# ProPrj_esp32_pressure_sensor_2026-01-26.net
KiCad netlist of a schematic drawn in EasyEDA Pro
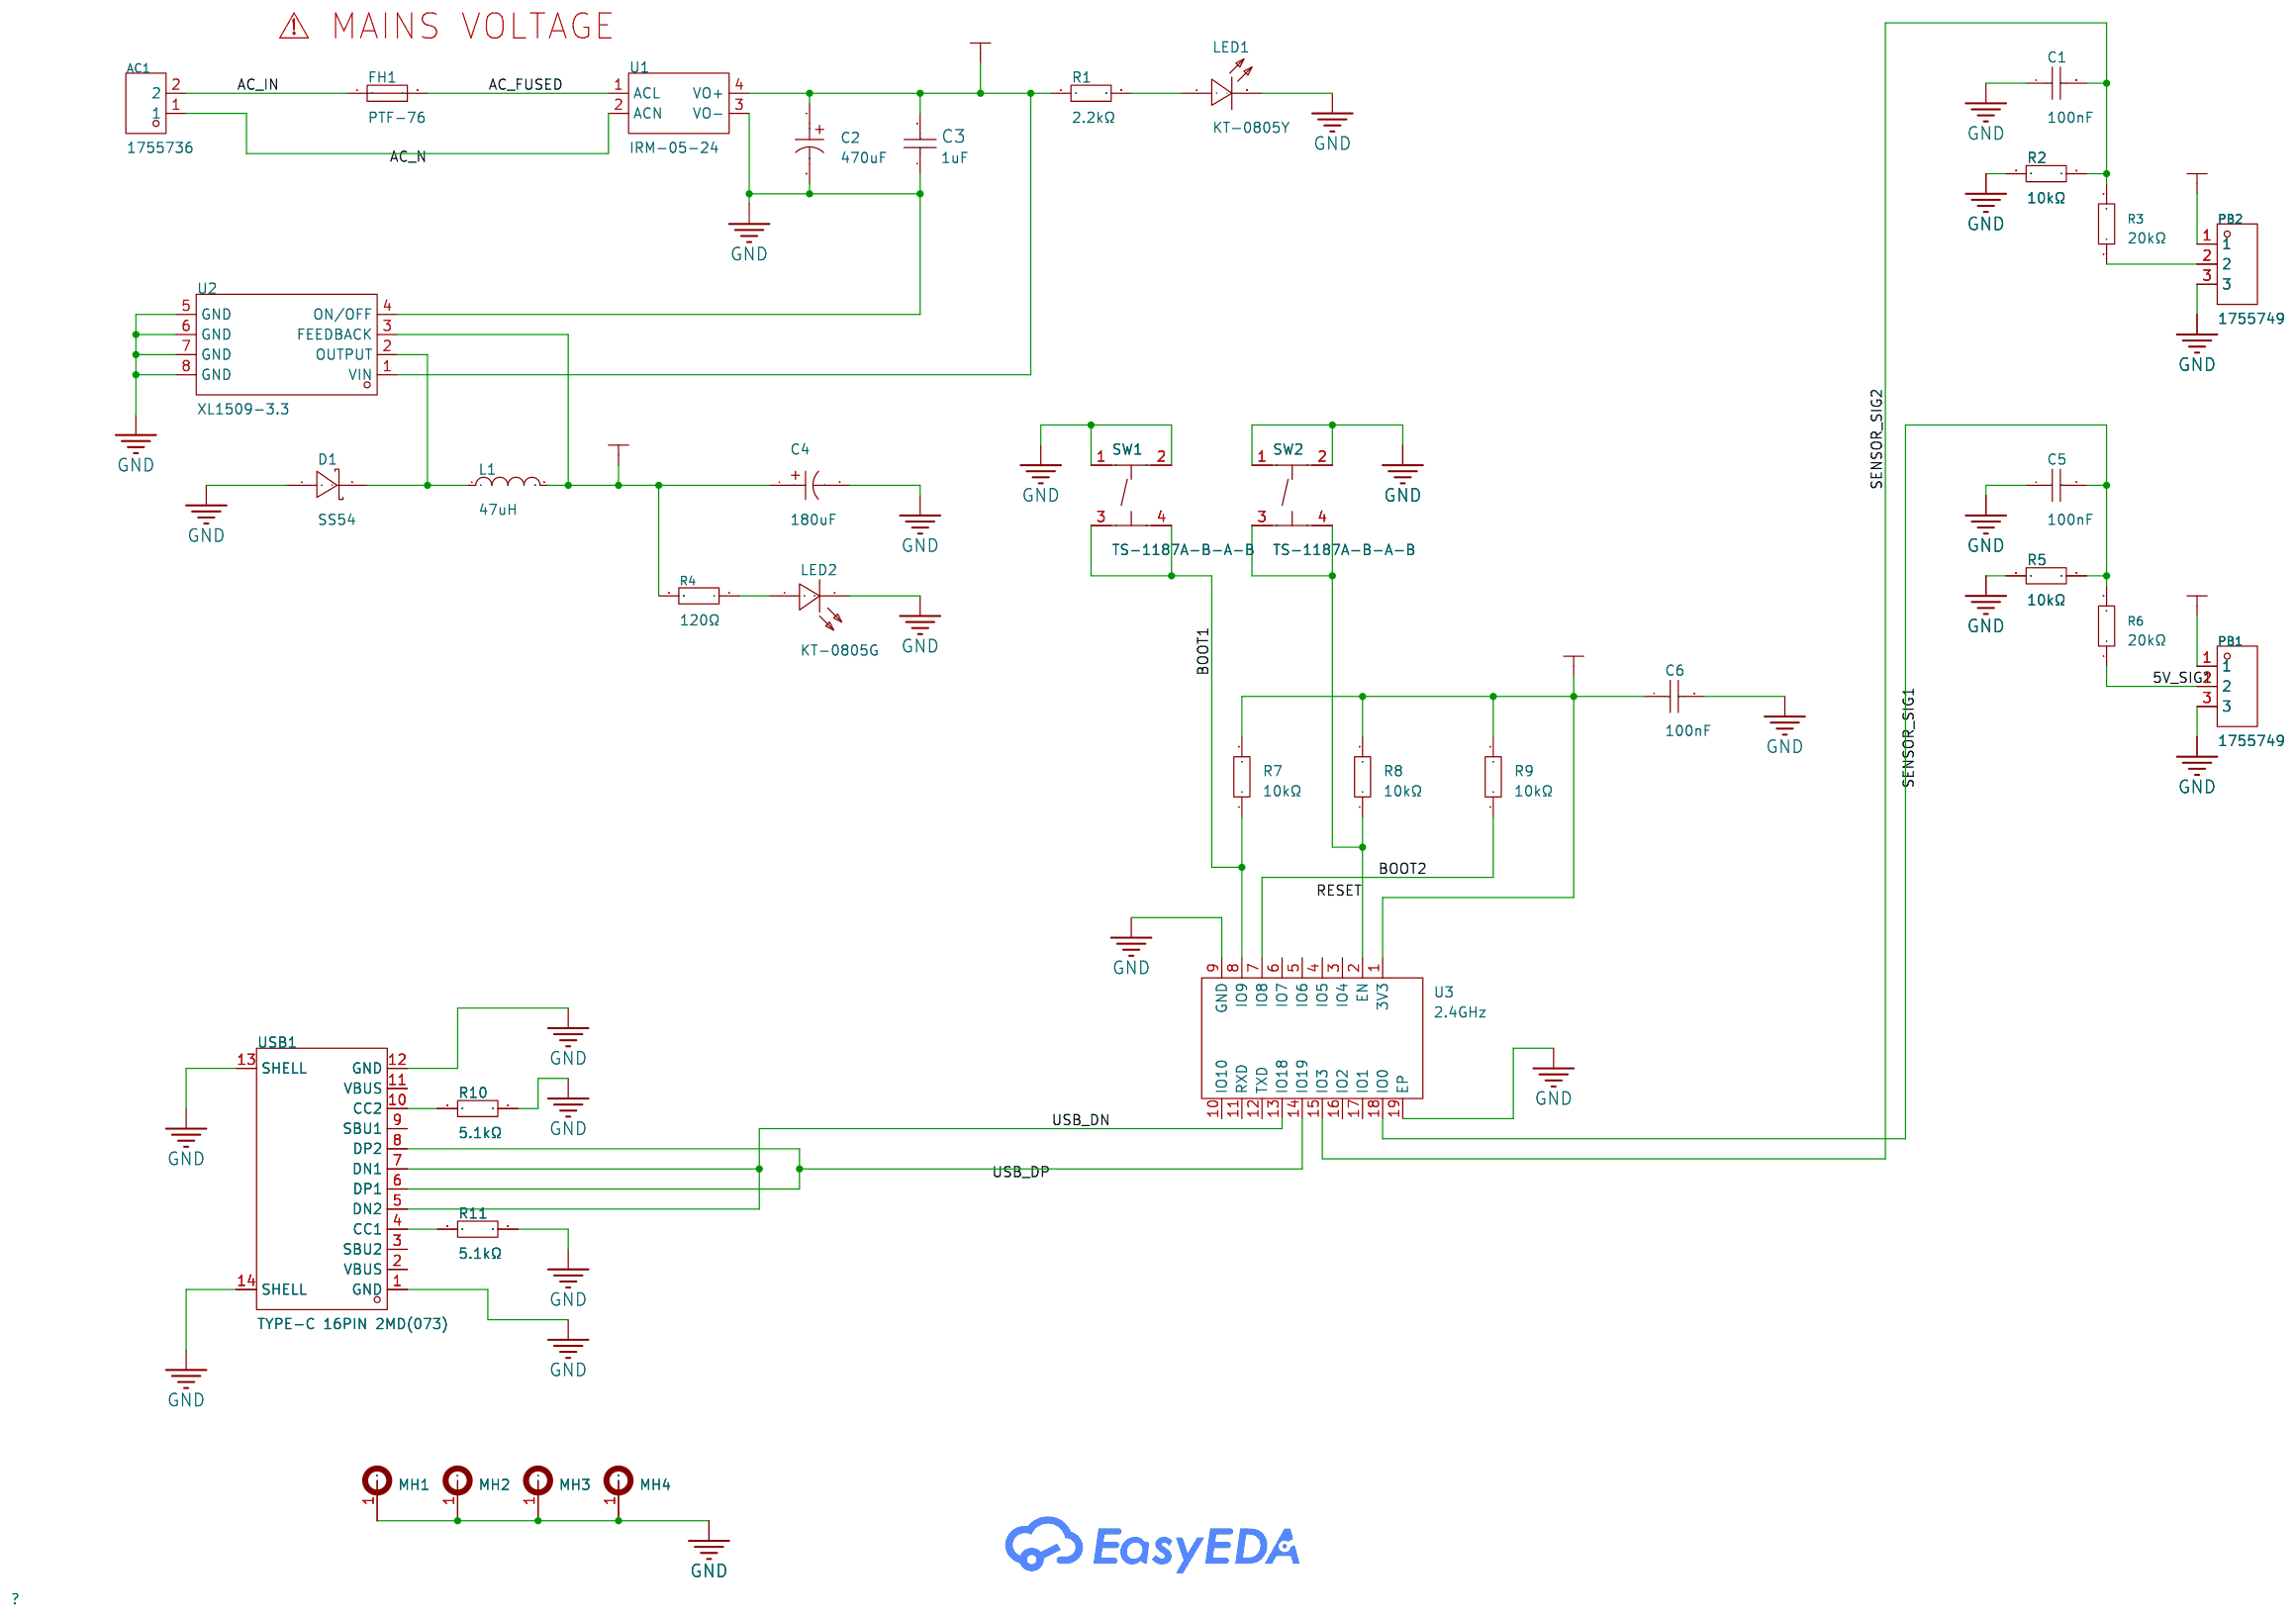
[diagram p0: schematic sheet]

(export (version "E")
  (design (tool "Eeschema 10.0.6"))
  (components
    (comp (ref "AC1")
      (value "1755736")
      (footprint "easyedapro:CONN-TH_1755736")
      (fields (field (name "Manufacturer") "Phoenix Contact(菲尼克斯)"))
      (libsource (lib "easyedapro") (part "1755736"))
    )
    (comp (ref "C1")
      (value "100nF")
      (footprint "easyedapro:C0805")
      (description "Capacitance:100nF Tolerance:±10% Tolerance:±10% Voltage Rating:100V Temperature Coefficient:X7R")
      (fields
        (field (name "Manufacturer Part") "CL21B104KCFNNNE")
        (field (name "Manufacturer") "SAMSUNG(三星)")
      )
      (libsource (lib "easyedapro") (part "CL21B104KCFNNNE"))
    )
    (comp (ref "C2")
      (value "470uF")
      (footprint "easyedapro:CAP-SMD_BD10.0-L10.3-W10.3-LS11.0-FD")
      (fields (field (name "Manufacturer Part") "JVE25V470M10X10") (field (name "Manufacturer") "JIERR(捷而瑞)"))
      (libsource (lib "easyedapro") (part "JVE25V470M10X10"))
    )
    (comp (ref "C3")
      (value "1uF")
      (footprint "easyedapro:C0805")
      (description "Capacitance:1uF Tolerance:±10% Tolerance:±10% Voltage Rating:50V Temperature Coefficient:X7R")
      (fields
        (field (name "Manufacturer Part") "CL21B105KBFNNNE")
        (field (name "Manufacturer") "SAMSUNG(三星)")
      )
      (libsource (lib "easyedapro") (part "CL21B105KBFNNNE"))
    )
    (comp (ref "C4")
      (value "180uF")
      (footprint "easyedapro:CAP-SMD_BD6.3-L6.6-W6.6-LS7.4-FD")
      (fields (field (name "Manufacturer Part") "RVT25V180M6X8") (field (name "Manufacturer") "JIERR(捷而瑞)"))
      (libsource (lib "easyedapro") (part "RVT25V180M6X8"))
    )
    (comp (ref "C5")
      (value "100nF")
      (footprint "easyedapro:C0805")
      (description "Capacitance:100nF Tolerance:±10% Tolerance:±10% Voltage Rating:100V Temperature Coefficient:X7R")
      (fields
        (field (name "Manufacturer Part") "CL21B104KCFNNNE")
        (field (name "Manufacturer") "SAMSUNG(三星)")
      )
      (libsource (lib "easyedapro") (part "CL21B104KCFNNNE"))
    )
    (comp (ref "C6")
      (value "100nF")
      (footprint "easyedapro:C0805")
      (description "Capacitance:100nF Tolerance:±10% Tolerance:±10% Voltage Rating:100V Temperature Coefficient:X7R")
      (fields
        (field (name "Manufacturer Part") "CL21B104KCFNNNE")
        (field (name "Manufacturer") "SAMSUNG(三星)")
      )
      (libsource (lib "easyedapro") (part "CL21B104KCFNNNE"))
    )
    (comp (ref "D1")
      (value "SS54")
      (footprint "easyedapro:SMA_L4.4-W2.8-LS5.4-R-RD")
      (fields (field (name "Manufacturer") "MDD(辰达半导体)"))
      (libsource (lib "easyedapro") (part "SS54_C22452"))
    )
    (comp (ref "FH1")
      (value "PTF-76")
      (footprint "easyedapro:FUSE-TH_L25.2-W9.8_PTF-76")
      (fields (field (name "Manufacturer") "XFCN(兴飞)"))
      (libsource (lib "easyedapro") (part "PTF-76"))
    )
    (comp (ref "L1")
      (value "47uH")
      (footprint "easyedapro:IND-SMD_L4.5-W4.0")
      (fields (field (name "Manufacturer Part") "CY43-47UH") (field (name "Manufacturer") "SHOU HAN(首韩)"))
      (libsource (lib "easyedapro") (part "CY43-47UH"))
    )
    (comp (ref "LED1")
      (value "KT-0805Y")
      (footprint "easyedapro:LED0805-R-RD")
      (fields (field (name "Manufacturer") "KENTO"))
      (libsource (lib "easyedapro") (part "17-21SUYC/TR8"))
    )
    (comp (ref "LED2")
      (value "KT-0805G")
      (footprint "easyedapro:LED0805-R-RD")
      (fields (field (name "Manufacturer") "KENTO"))
      (libsource (lib "easyedapro") (part "0805G (Green)"))
    )
    (comp (ref "MH1")
      (value "~")
      (footprint "easyedapro:MH_7.5x2.7mm")
      (libsource (lib "easyedapro") (part "MH_7.5x2.7mm"))
    )
    (comp (ref "MH2")
      (value "~")
      (footprint "easyedapro:MH_7.5x2.7mm")
      (libsource (lib "easyedapro") (part "MH_7.5x2.7mm"))
    )
    (comp (ref "MH3")
      (value "~")
      (footprint "easyedapro:MH_7.5x2.7mm")
      (libsource (lib "easyedapro") (part "MH_7.5x2.7mm"))
    )
    (comp (ref "MH4")
      (value "~")
      (footprint "easyedapro:MH_7.5x2.7mm")
      (libsource (lib "easyedapro") (part "MH_7.5x2.7mm"))
    )
    (comp (ref "PB1")
      (value "1755749")
      (footprint "easyedapro:CONN-TH_1755749")
      (fields (field (name "Manufacturer") "Phoenix Contact(菲尼克斯)"))
      (libsource (lib "easyedapro") (part "1755749"))
    )
    (comp (ref "PB2")
      (value "1755749")
      (footprint "easyedapro:CONN-TH_1755749")
      (fields (field (name "Manufacturer") "Phoenix Contact(菲尼克斯)"))
      (libsource (lib "easyedapro") (part "1755749"))
    )
    (comp (ref "R1")
      (value "2.2kΩ")
      (footprint "easyedapro:R0805")
      (fields
        (field (name "Manufacturer Part") "0805W8F2201T5E")
        (field (name "Manufacturer") "UNI-ROYAL(厚声)")
      )
      (libsource (lib "easyedapro") (part "0805W8F2201T5E"))
    )
    (comp (ref "R2")
      (value "10kΩ")
      (footprint "easyedapro:R0805")
      (fields
        (field (name "Manufacturer Part") "0805W8F1002T5E")
        (field (name "Manufacturer") "UNI-ROYAL(厚声)")
      )
      (libsource (lib "easyedapro") (part "0805W8F1002T5E"))
    )
    (comp (ref "R3")
      (value "20kΩ")
      (footprint "easyedapro:R0805")
      (fields
        (field (name "Manufacturer Part") "0805W8F2002T5E")
        (field (name "Manufacturer") "UNI-ROYAL(厚声)")
      )
      (libsource (lib "easyedapro") (part "0805W8F2002T5E"))
    )
    (comp (ref "R4")
      (value "120Ω")
      (footprint "easyedapro:R0805")
      (fields
        (field (name "Manufacturer Part") "0805W8F1200T5E")
        (field (name "Manufacturer") "UNI-ROYAL(厚声)")
      )
      (libsource (lib "easyedapro") (part "0805W8F1200T5E"))
    )
    (comp (ref "R5")
      (value "10kΩ")
      (footprint "easyedapro:R0805")
      (fields
        (field (name "Manufacturer Part") "0805W8F1002T5E")
        (field (name "Manufacturer") "UNI-ROYAL(厚声)")
      )
      (libsource (lib "easyedapro") (part "0805W8F1002T5E"))
    )
    (comp (ref "R6")
      (value "20kΩ")
      (footprint "easyedapro:R0805")
      (fields
        (field (name "Manufacturer Part") "0805W8F2002T5E")
        (field (name "Manufacturer") "UNI-ROYAL(厚声)")
      )
      (libsource (lib "easyedapro") (part "0805W8F2002T5E"))
    )
    (comp (ref "R7")
      (value "10kΩ")
      (footprint "easyedapro:R0805")
      (fields
        (field (name "Manufacturer Part") "0805W8F1002T5E")
        (field (name "Manufacturer") "UNI-ROYAL(厚声)")
      )
      (libsource (lib "easyedapro") (part "0805W8F1002T5E"))
    )
    (comp (ref "R8")
      (value "10kΩ")
      (footprint "easyedapro:R0805")
      (fields
        (field (name "Manufacturer Part") "0805W8F1002T5E")
        (field (name "Manufacturer") "UNI-ROYAL(厚声)")
      )
      (libsource (lib "easyedapro") (part "0805W8F1002T5E"))
    )
    (comp (ref "R9")
      (value "10kΩ")
      (footprint "easyedapro:R0805")
      (fields
        (field (name "Manufacturer Part") "0805W8F1002T5E")
        (field (name "Manufacturer") "UNI-ROYAL(厚声)")
      )
      (libsource (lib "easyedapro") (part "0805W8F1002T5E"))
    )
    (comp (ref "R10")
      (value "5.1kΩ")
      (footprint "easyedapro:R0805")
      (fields
        (field (name "Manufacturer Part") "0805W8F5101T5E")
        (field (name "Manufacturer") "UNI-ROYAL(厚声)")
      )
      (libsource (lib "easyedapro") (part "0805W8F5101T5E"))
    )
    (comp (ref "R11")
      (value "5.1kΩ")
      (footprint "easyedapro:R0805")
      (fields
        (field (name "Manufacturer Part") "0805W8F5101T5E")
        (field (name "Manufacturer") "UNI-ROYAL(厚声)")
      )
      (libsource (lib "easyedapro") (part "0805W8F5101T5E"))
    )
    (comp (ref "SW1")
      (value "TS-1187A-B-A-B")
      (footprint "easyedapro:SW-SMD_4P-L5.1-W5.1-P3.70-LS6.5-TL_H1.5")
      (fields (field (name "Manufacturer") "XKB Connection(中国星坤)"))
      (libsource (lib "easyedapro") (part "TS-1187A-B-A-B"))
    )
    (comp (ref "SW2")
      (value "TS-1187A-B-A-B")
      (footprint "easyedapro:SW-SMD_4P-L5.1-W5.1-P3.70-LS6.5-TL_H1.5")
      (fields (field (name "Manufacturer") "XKB Connection(中国星坤)"))
      (libsource (lib "easyedapro") (part "TS-1187A-B-A-B"))
    )
    (comp (ref "U1")
      (value "IRM-05-24")
      (footprint "easyedapro:PWRM-TH_IRM-05-XX")
      (fields (field (name "Manufacturer") "MW(明纬)"))
      (libsource (lib "easyedapro") (part "IRM-05-24"))
    )
    (comp (ref "U2")
      (value "XL1509-3.3")
      (footprint "easyedapro:SOIC-8_L4.9-W3.9-P1.27-LS6.0-BL")
      (fields (field (name "Manufacturer") "UMW(友台半导体)"))
      (libsource (lib "easyedapro") (part "XL1509-3.3"))
    )
    (comp (ref "U3")
      (value "2.4GHz")
      (footprint "easyedapro:BULETM-SMD_ESPRESSIF_ESP32-C3-WROOM-02-N4-4MB")
      (fields
        (field (name "Manufacturer Part") "ESP32-C3-WROOM-02-N4")
        (field (name "Manufacturer") "ESPRESSIF(乐鑫)")
      )
      (libsource (lib "easyedapro") (part "ESP32-C3-WROOM-02-N4(4MB)"))
    )
    (comp (ref "USB1")
      (value "TYPE-C 16PIN 2MD(073)")
      (footprint "easyedapro:USB-C-SMD_TYPE-C-6PIN-2MD-073")
      (fields (field (name "Manufacturer") "SHOU HAN(首韩)"))
      (libsource (lib "easyedapro") (part "TYPE-C 16PIN 2MD(073)"))
    )
  )
  (nets
    (net (code "1") (name "+3.3V") (class "Default")
      (node (ref "C4") (pin "1") (pinfunction "1_1") (pintype "input"))
      (node (ref "C6") (pin "1") (pinfunction "1_1") (pintype "input"))
      (node (ref "L1") (pin "2") (pinfunction "2_2") (pintype "unspecified"))
      (node (ref "R4") (pin "2") (pinfunction "2_2") (pintype "input"))
      (node (ref "R7") (pin "2") (pinfunction "2_2") (pintype "input"))
      (node (ref "R8") (pin "2") (pinfunction "2_2") (pintype "input"))
      (node (ref "R9") (pin "2") (pinfunction "2_2") (pintype "input"))
      (node (ref "U2") (pin "3") (pinfunction "FEEDBACK_3") (pintype "unspecified"))
      (node (ref "U3") (pin "1") (pinfunction "3V3_1") (pintype "unspecified"))
    )
    (net (code "2") (name "+24V") (class "Default")
      (node (ref "C2") (pin "1") (pinfunction "1_1") (pintype "input"))
      (node (ref "C3") (pin "2") (pinfunction "2_2") (pintype "input"))
      (node (ref "PB1") (pin "1") (pinfunction "1_1") (pintype "input"))
      (node (ref "PB2") (pin "1") (pinfunction "1_1") (pintype "input"))
      (node (ref "R1") (pin "1") (pinfunction "1_1") (pintype "input"))
      (node (ref "U1") (pin "4") (pinfunction "VO+_4") (pintype "unspecified"))
      (node (ref "U2") (pin "1") (pinfunction "VIN_1") (pintype "unspecified"))
    )
    (net (code "3") (name "/5V_SIG1") (class "Default")
      (node (ref "PB1") (pin "2") (pinfunction "2_2") (pintype "input"))
      (node (ref "R6") (pin "1") (pinfunction "1_1") (pintype "input"))
    )
    (net (code "4") (name "/AC_FUSED") (class "Default")
      (node (ref "FH1") (pin "2") (pinfunction "2_2") (pintype "unspecified"))
      (node (ref "U1") (pin "1") (pinfunction "ACL_1") (pintype "unspecified"))
    )
    (net (code "5") (name "/AC_IN") (class "Default")
      (node (ref "AC1") (pin "2") (pinfunction "2_2") (pintype "input"))
      (node (ref "FH1") (pin "1") (pinfunction "1_1") (pintype "unspecified"))
    )
    (net (code "6") (name "/AC_N") (class "Default")
      (node (ref "AC1") (pin "1") (pinfunction "1_1") (pintype "input"))
      (node (ref "U1") (pin "2") (pinfunction "ACN_2") (pintype "unspecified"))
    )
    (net (code "7") (name "/BOOT1") (class "Default")
      (node (ref "R7") (pin "1") (pinfunction "1_1") (pintype "input"))
      (node (ref "SW1") (pin "3") (pinfunction "C_3") (pintype "unspecified"))
      (node (ref "SW1") (pin "4") (pinfunction "D_4") (pintype "unspecified"))
      (node (ref "U3") (pin "8") (pinfunction "IO9_8") (pintype "unspecified"))
    )
    (net (code "8") (name "/BOOT2") (class "Default")
      (node (ref "R9") (pin "1") (pinfunction "1_1") (pintype "input"))
      (node (ref "U3") (pin "7") (pinfunction "IO8_7") (pintype "unspecified"))
    )
    (net (code "9") (name "/RESET") (class "Default")
      (node (ref "R8") (pin "1") (pinfunction "1_1") (pintype "input"))
      (node (ref "SW2") (pin "3") (pinfunction "C_3") (pintype "unspecified"))
      (node (ref "SW2") (pin "4") (pinfunction "D_4") (pintype "unspecified"))
      (node (ref "U3") (pin "2") (pinfunction "EN_2") (pintype "unspecified"))
    )
    (net (code "10") (name "/SENSOR_SIG1") (class "Default")
      (node (ref "C5") (pin "2") (pinfunction "2_2") (pintype "input"))
      (node (ref "R5") (pin "1") (pinfunction "1_1") (pintype "input"))
      (node (ref "R6") (pin "2") (pinfunction "2_2") (pintype "input"))
      (node (ref "U3") (pin "18") (pinfunction "IO0_18") (pintype "unspecified"))
    )
    (net (code "11") (name "/SENSOR_SIG2") (class "Default")
      (node (ref "C1") (pin "2") (pinfunction "2_2") (pintype "input"))
      (node (ref "R2") (pin "1") (pinfunction "1_1") (pintype "input"))
      (node (ref "R3") (pin "2") (pinfunction "2_2") (pintype "input"))
      (node (ref "U3") (pin "15") (pinfunction "IO3_15") (pintype "unspecified"))
    )
    (net (code "12") (name "/USB_DN") (class "Default")
      (node (ref "U3") (pin "13") (pinfunction "IO18_13") (pintype "unspecified"))
      (node (ref "USB1") (pin "5") (pinfunction "DN2_5") (pintype "unspecified"))
      (node (ref "USB1") (pin "7") (pinfunction "DN1_7") (pintype "unspecified"))
    )
    (net (code "13") (name "/USB_DP") (class "Default")
      (node (ref "U3") (pin "14") (pinfunction "IO19_14") (pintype "unspecified"))
      (node (ref "USB1") (pin "6") (pinfunction "DP1_6") (pintype "unspecified"))
      (node (ref "USB1") (pin "8") (pinfunction "DP2_8") (pintype "unspecified"))
    )
    (net (code "14") (name "GND") (class "Default")
      (node (ref "C1") (pin "1") (pinfunction "1_1") (pintype "input"))
      (node (ref "C2") (pin "2") (pinfunction "2_2") (pintype "input"))
      (node (ref "C3") (pin "1") (pinfunction "1_1") (pintype "input"))
      (node (ref "C4") (pin "2") (pinfunction "2_2") (pintype "input"))
      (node (ref "C5") (pin "1") (pinfunction "1_1") (pintype "input"))
      (node (ref "C6") (pin "2") (pinfunction "2_2") (pintype "input"))
      (node (ref "D1") (pin "1") (pinfunction "A_1") (pintype "unspecified"))
      (node (ref "LED1") (pin "2") (pinfunction "-_2") (pintype "unspecified"))
      (node (ref "LED2") (pin "2") (pinfunction "K_2") (pintype "unspecified"))
      (node (ref "MH1") (pin "1") (pinfunction "1_1") (pintype "input"))
      (node (ref "MH2") (pin "1") (pinfunction "1_1") (pintype "input"))
      (node (ref "MH3") (pin "1") (pinfunction "1_1") (pintype "input"))
      (node (ref "MH4") (pin "1") (pinfunction "1_1") (pintype "input"))
      (node (ref "PB1") (pin "3") (pinfunction "3_3") (pintype "input"))
      (node (ref "PB2") (pin "3") (pinfunction "3_3") (pintype "input"))
      (node (ref "R10") (pin "1") (pinfunction "1_1") (pintype "input"))
      (node (ref "R11") (pin "1") (pinfunction "1_1") (pintype "input"))
      (node (ref "R2") (pin "2") (pinfunction "2_2") (pintype "input"))
      (node (ref "R5") (pin "2") (pinfunction "2_2") (pintype "input"))
      (node (ref "SW1") (pin "1") (pinfunction "A_1") (pintype "unspecified"))
      (node (ref "SW1") (pin "2") (pinfunction "B_2") (pintype "unspecified"))
      (node (ref "SW2") (pin "1") (pinfunction "A_1") (pintype "unspecified"))
      (node (ref "SW2") (pin "2") (pinfunction "B_2") (pintype "unspecified"))
      (node (ref "U1") (pin "3") (pinfunction "VO-_3") (pintype "unspecified"))
      (node (ref "U2") (pin "4") (pinfunction "ON/OFF_4") (pintype "unspecified"))
      (node (ref "U2") (pin "5") (pinfunction "GND_5") (pintype "unspecified"))
      (node (ref "U2") (pin "6") (pinfunction "GND_6") (pintype "unspecified"))
      (node (ref "U2") (pin "7") (pinfunction "GND_7") (pintype "unspecified"))
      (node (ref "U2") (pin "8") (pinfunction "GND_8") (pintype "unspecified"))
      (node (ref "U3") (pin "19") (pinfunction "EP_19") (pintype "unspecified"))
      (node (ref "U3") (pin "9") (pinfunction "GND_9") (pintype "unspecified"))
      (node (ref "USB1") (pin "1") (pinfunction "GND_1") (pintype "unspecified"))
      (node (ref "USB1") (pin "12") (pinfunction "GND_12") (pintype "unspecified"))
      (node (ref "USB1") (pin "13") (pinfunction "SHELL_13") (pintype "unspecified"))
      (node (ref "USB1") (pin "14") (pinfunction "SHELL_14") (pintype "unspecified"))
    )
    (net (code "15") (name "Net-(D1-K)") (class "Default")
      (node (ref "D1") (pin "2") (pinfunction "K_2") (pintype "unspecified"))
      (node (ref "L1") (pin "1") (pinfunction "1_1") (pintype "unspecified"))
      (node (ref "U2") (pin "2") (pinfunction "OUTPUT_2") (pintype "unspecified"))
    )
    (net (code "16") (name "Net-(LED1-+)") (class "Default")
      (node (ref "LED1") (pin "1") (pinfunction "+_1") (pintype "unspecified"))
      (node (ref "R1") (pin "2") (pinfunction "2_2") (pintype "input"))
    )
    (net (code "17") (name "Net-(LED2-A)") (class "Default")
      (node (ref "LED2") (pin "1") (pinfunction "A_1") (pintype "unspecified"))
      (node (ref "R4") (pin "1") (pinfunction "1_1") (pintype "input"))
    )
    (net (code "18") (name "Net-(PB2-Pad2)") (class "Default")
      (node (ref "PB2") (pin "2") (pinfunction "2_2") (pintype "input"))
      (node (ref "R3") (pin "1") (pinfunction "1_1") (pintype "input"))
    )
    (net (code "19") (name "Net-(USB1-CC1)") (class "Default")
      (node (ref "R11") (pin "2") (pinfunction "2_2") (pintype "input"))
      (node (ref "USB1") (pin "4") (pinfunction "CC1_4") (pintype "unspecified"))
    )
    (net (code "20") (name "Net-(USB1-CC2)") (class "Default")
      (node (ref "R10") (pin "2") (pinfunction "2_2") (pintype "input"))
      (node (ref "USB1") (pin "10") (pinfunction "CC2_10") (pintype "unspecified"))
    )
    (net (code "21") (name "unconnected-(U3-IO1-Pad17)") (class "Default")
      (node (ref "U3") (pin "17") (pinfunction "IO1_17") (pintype "unspecified"))
    )
    (net (code "22") (name "unconnected-(U3-IO2-Pad16)") (class "Default")
      (node (ref "U3") (pin "16") (pinfunction "IO2_16") (pintype "unspecified"))
    )
    (net (code "23") (name "unconnected-(U3-IO4-Pad3)") (class "Default")
      (node (ref "U3") (pin "3") (pinfunction "IO4_3") (pintype "unspecified"))
    )
    (net (code "24") (name "unconnected-(U3-IO5-Pad4)") (class "Default")
      (node (ref "U3") (pin "4") (pinfunction "IO5_4") (pintype "unspecified"))
    )
    (net (code "25") (name "unconnected-(U3-IO6-Pad5)") (class "Default")
      (node (ref "U3") (pin "5") (pinfunction "IO6_5") (pintype "unspecified"))
    )
    (net (code "26") (name "unconnected-(U3-IO7-Pad6)") (class "Default")
      (node (ref "U3") (pin "6") (pinfunction "IO7_6") (pintype "unspecified"))
    )
    (net (code "27") (name "unconnected-(U3-IO10-Pad10)") (class "Default")
      (node (ref "U3") (pin "10") (pinfunction "IO10_10") (pintype "unspecified"))
    )
    (net (code "28") (name "unconnected-(U3-RXD-Pad11)") (class "Default")
      (node (ref "U3") (pin "11") (pinfunction "RXD_11") (pintype "unspecified"))
    )
    (net (code "29") (name "unconnected-(U3-TXD-Pad12)") (class "Default")
      (node (ref "U3") (pin "12") (pinfunction "TXD_12") (pintype "unspecified"))
    )
    (net (code "30") (name "unconnected-(USB1-SBU1-Pad9)") (class "Default")
      (node (ref "USB1") (pin "9") (pinfunction "SBU1_9") (pintype "unspecified"))
    )
    (net (code "31") (name "unconnected-(USB1-SBU2-Pad3)") (class "Default")
      (node (ref "USB1") (pin "3") (pinfunction "SBU2_3") (pintype "unspecified"))
    )
    (net (code "32") (name "unconnected-(USB1-VBUS-Pad2)") (class "Default")
      (node (ref "USB1") (pin "2") (pinfunction "VBUS_2") (pintype "unspecified"))
    )
    (net (code "33") (name "unconnected-(USB1-VBUS-Pad11)") (class "Default")
      (node (ref "USB1") (pin "11") (pinfunction "VBUS_11") (pintype "unspecified"))
    )
  )
)
